# Sheet2.net
KiCad netlist of a schematic drawn in Altium Designer
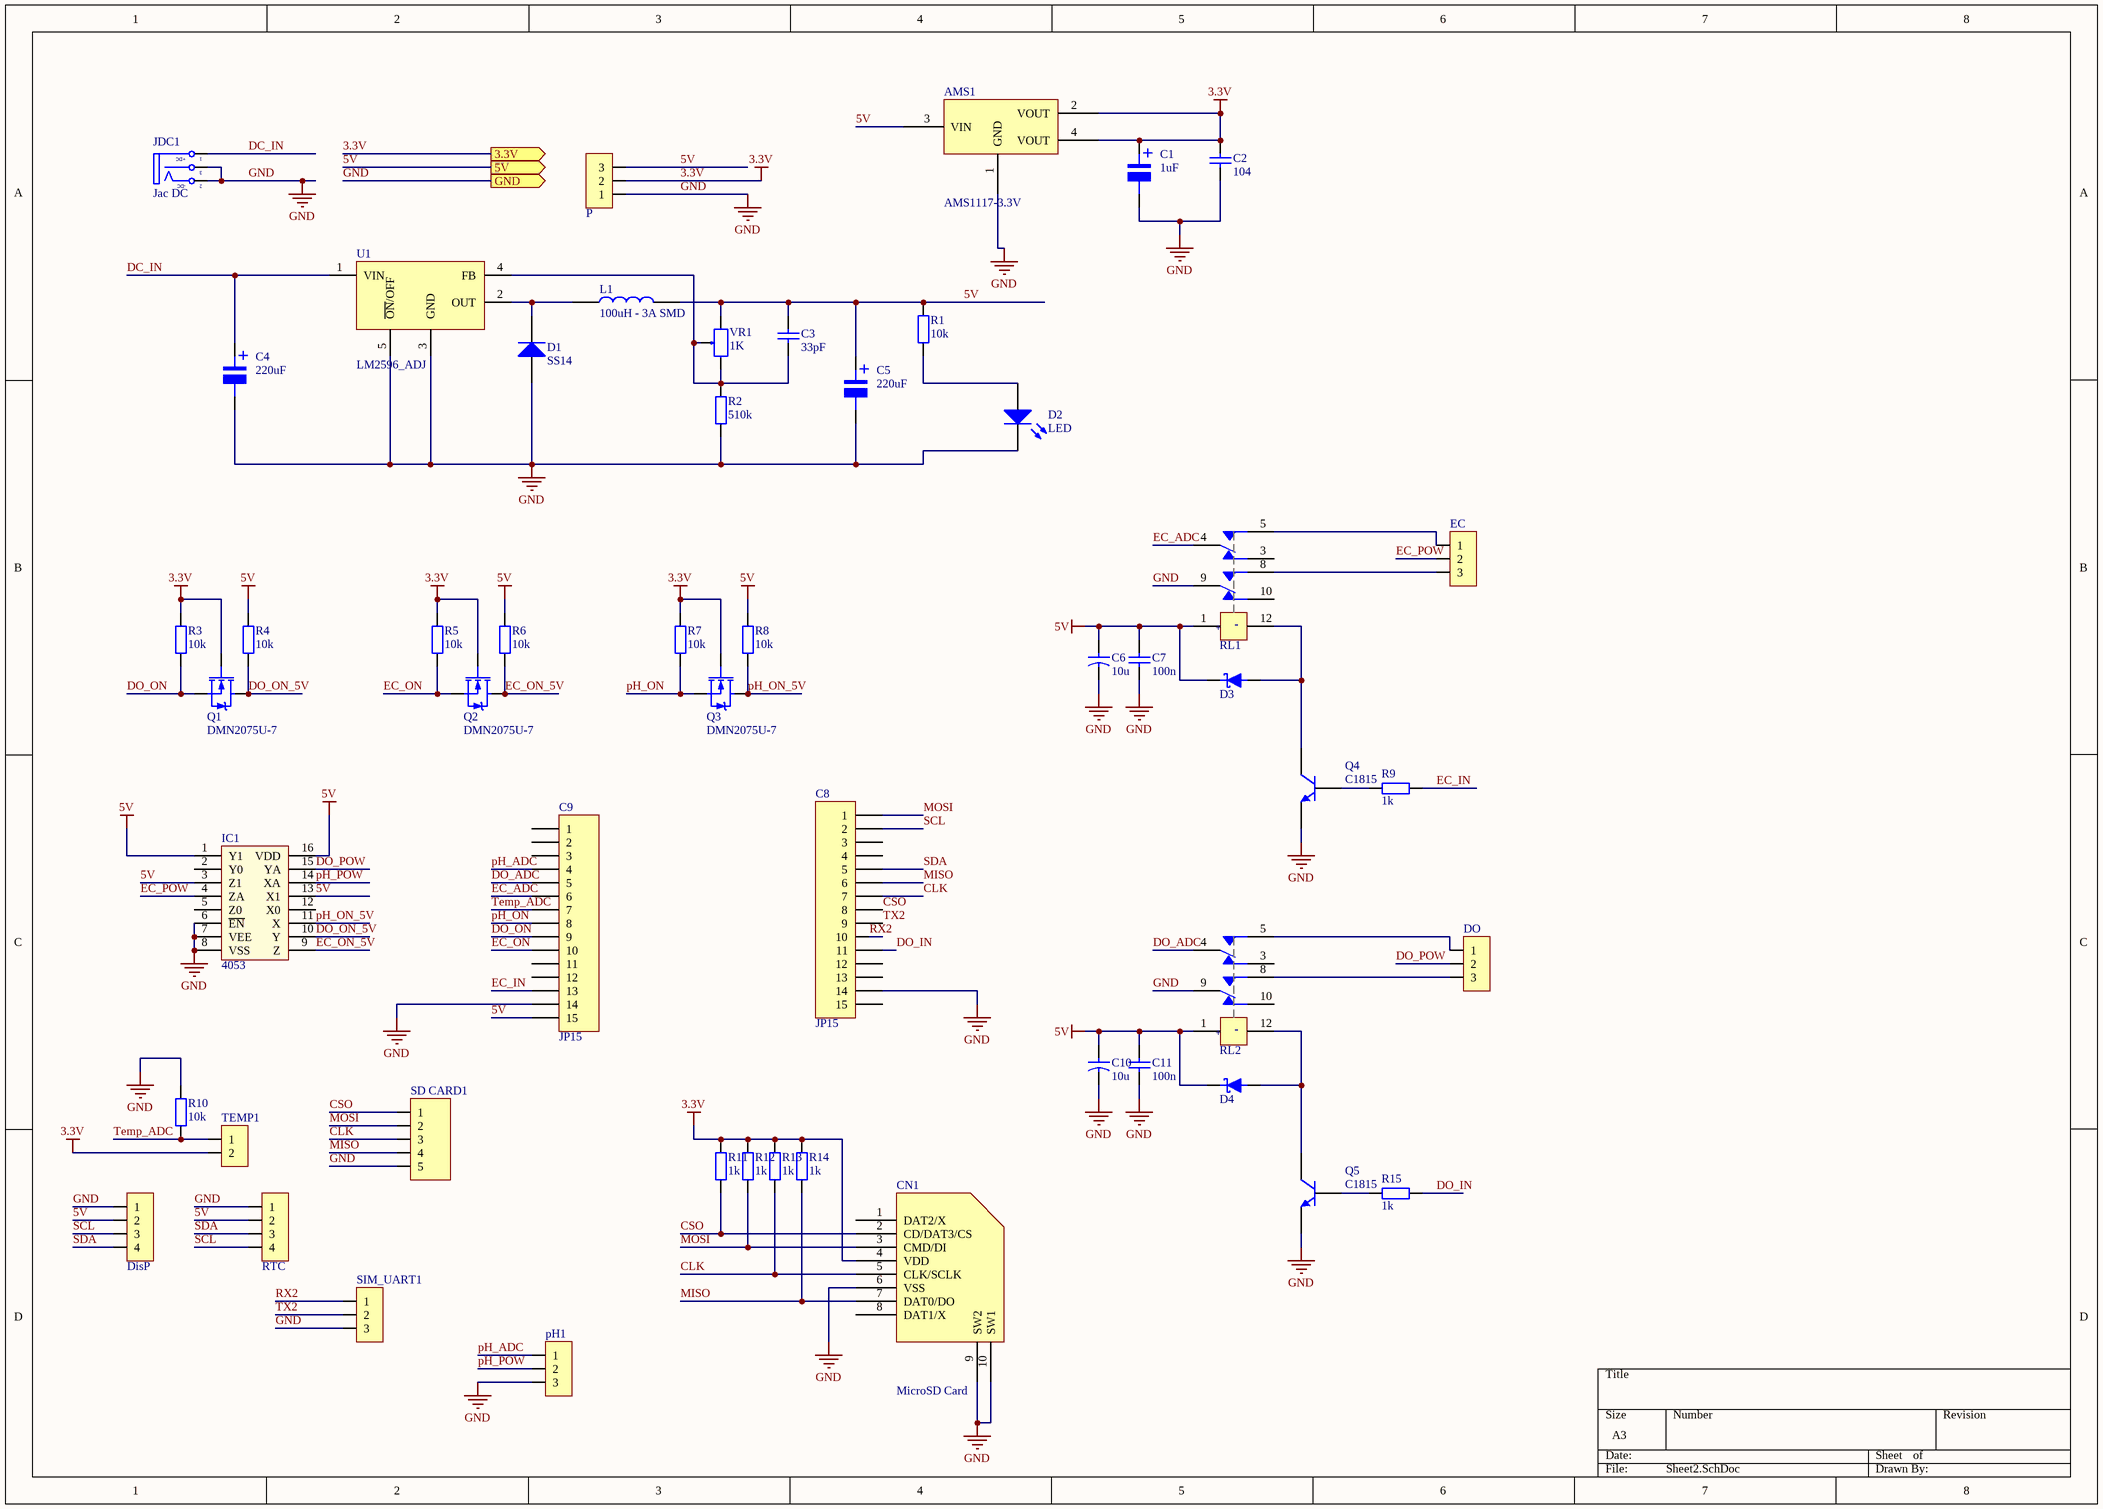
[diagram p0: Sheet2.SchDoc]

(export (version "E")
  (design (tool "Eeschema 10.0.6"))
  (components
    (comp (ref "AMS1")
      (value "AMS1117-3.3V")
      (footprint "SOT223")
      (description "Dán")
      (libsource (lib "bkres_POW") (part "AMS1117 SMD"))
    )
    (comp (ref "C1")
      (value "1uF")
      (footprint "tu nhom 4 (B)")
      (description "Dán")
      (libsource (lib "bkres_POW") (part "Tu Nhom 1uF 50V"))
    )
    (comp (ref "C2")
      (value "104")
      (footprint "tu 0805")
      (description "Dán")
      (libsource (lib "bkres_POW") (part "Tu 0805 104 50V 10%"))
    )
    (comp (ref "C3")
      (value "33pF")
      (footprint "tu 0805")
      (description "Dán")
      (libsource (lib "bkres_POW") (part "Tu 0805 33pF 50V 10%"))
    )
    (comp (ref "C4")
      (value "220uF")
      (footprint "tu nhom 6.3 (d)")
      (description "Dán")
      (libsource (lib "bkres_POW") (part "Tu Nhom 220uF 16V"))
    )
    (comp (ref "C5")
      (value "220uF")
      (footprint "tu nhom 6.3 (d)")
      (description "Dán")
      (libsource (lib "bkres_POW") (part "Tu Nhom 220uF 16V"))
    )
    (comp (ref "C6")
      (value "10u")
      (footprint "CT1206")
      (description "Polar Capacitor")
      (fields (field (name "Comment") "C-P"))
      (libsource (lib "Conductivity") (part "C-P"))
    )
    (comp (ref "C7")
      (value "100n")
      (footprint "CC0805L")
      (description "Non-Polar Capacitor")
      (fields (field (name "Comment") "C-N"))
      (libsource (lib "Conductivity") (part "C-N"))
    )
    (comp (ref "C8")
      (value "JP15")
      (footprint "JP15-C1T")
      (description "WR-PHD 2.54 mm Angled Socket Header")
      (fields
        (field (name "MANUFACTURER") "Würth Elektronik eiSos GmbH")
        (field (name "PARTNO") "613015143121")
        (field (name "CREATED BY") "Karrer Zheng")
      )
      (libsource (lib "") (part "JP15_1"))
    )
    (comp (ref "C9")
      (value "JP15")
      (footprint "JP15-C1T")
      (description "WR-PHD 2.54 mm Angled Socket Header")
      (fields
        (field (name "MANUFACTURER") "Würth Elektronik eiSos GmbH")
        (field (name "PARTNO") "613015143121")
        (field (name "CREATED BY") "Karrer Zheng")
      )
      (libsource (lib "LIBRARY") (part "JP15"))
    )
    (comp (ref "C10")
      (value "10u")
      (footprint "CT1206")
      (description "Polar Capacitor")
      (fields (field (name "Comment") "C-P"))
      (libsource (lib "Conductivity") (part "C-P"))
    )
    (comp (ref "C11")
      (value "100n")
      (footprint "CC0805L")
      (description "Non-Polar Capacitor")
      (fields (field (name "Comment") "C-N"))
      (libsource (lib "Conductivity") (part "C-N"))
    )
    (comp (ref "CN1")
      (value "MicroSD Card")
      (footprint "MicroSD Card")
      (libsource (lib "PCB_Project_5") (part "MicroSD Card"))
    )
    (comp (ref "D1")
      (value "SS14")
      (footprint "DIODE SMA")
      (description "Dán")
      (libsource (lib "bkres_POW") (part "Diode SS14 ( 1N5819)"))
    )
    (comp (ref "D2")
      (value "LED")
      (footprint "LED-0805-Red")
      (description "Typical INFRARED GaAs LED")
      (fields (field (name "PUBLISHER") "Altium Limited"))
      (libsource (lib "bkres_POW") (part "LED"))
    )
    (comp (ref "D3")
      (value "D Schottky")
      (footprint "DO-214AC")
      (description "Schottky Diode")
      (libsource (lib "Conductivity") (part "D Schottky"))
    )
    (comp (ref "D4")
      (value "D Schottky")
      (footprint "DO-214AC")
      (description "Schottky Diode")
      (libsource (lib "Conductivity") (part "D Schottky"))
    )
    (comp (ref "IC1")
      (value "4053")
      (footprint "SO16")
      (description "Dual 4-channel analogue  multiplexer/demultiplexer")
      (libsource (lib "TechMT.VN_Lib_Project v2") (part "4053"))
    )
    (comp (ref "JDC1")
      (value "Jac DC")
      (footprint "DC-IN")
      (description "Jac DC input")
      (libsource (lib "bkres_POW") (part "DCIN"))
    )
    (comp (ref "JP1")
      (value "DisP")
      (footprint "JP 1x4 CT")
      (description "Cắm")
      (libsource (lib "Altium_Lib_by_KhueNguyenCreator") (part "JP 1x4 2.54 Cai Thang"))
    )
    (comp (ref "JP2")
      (value "EC")
      (footprint "JP 1x3 DT")
      (description "Cắm")
      (libsource (lib "Altium_Lib_by_KhueNguyenCreator") (part "JP 1x3 2.54 Duc Thang"))
    )
    (comp (ref "JP3")
      (value "DO")
      (footprint "JP 1x3 DT")
      (description "Cắm")
      (libsource (lib "Altium_Lib_by_KhueNguyenCreator") (part "JP 1x3 2.54 Duc Thang"))
    )
    (comp (ref "JP4")
      (value "RTC")
      (footprint "JP 1x4 CT")
      (description "Cắm")
      (libsource (lib "Altium_Lib_by_KhueNguyenCreator") (part "JP 1x4 2.54 Cai Thang"))
    )
    (comp (ref "L1")
      (value "100uH - 3A SMD")
      (footprint "Cuon Cam 12x12x10")
      (description "Dán")
      (libsource (lib "bkres_POW") (part "CUON CAM 100uH SMD"))
    )
    (comp (ref "P")
      (value "SIM_UART")
      (footprint "JP 1x3 DT")
      (description "Cắm")
      (libsource (lib "") (part "JP 1x3 2.54 Duc Thang_1"))
    )
    (comp (ref "pH1")
      (value "pH")
      (footprint "JP 1x3 DT")
      (description "Cắm")
      (libsource (lib "Altium_Lib_by_KhueNguyenCreator") (part "JP 1x3 2.54 Duc Thang"))
    )
    (comp (ref "Q1")
      (value "DMN2075U-7")
      (footprint "SOT23")
      (description "MOSFET N-CH 20V 4.2A SOT23")
      (fields (field (name "PUBLISHER") "Altium Limited"))
      (libsource (lib "PCB_Project_5") (part "DMN2075U-7"))
    )
    (comp (ref "Q2")
      (value "DMN2075U-7")
      (footprint "SOT23")
      (description "MOSFET N-CH 20V 4.2A SOT23")
      (fields (field (name "PUBLISHER") "Altium Limited"))
      (libsource (lib "PCB_Project_5") (part "DMN2075U-7"))
    )
    (comp (ref "Q3")
      (value "DMN2075U-7")
      (footprint "SOT23")
      (description "MOSFET N-CH 20V 4.2A SOT23")
      (fields (field (name "PUBLISHER") "Altium Limited"))
      (libsource (lib "PCB_Project_5") (part "DMN2075U-7"))
    )
    (comp (ref "Q4")
      (value "C1815")
      (footprint "SOT-23")
      (description "NPN G, 150mA, 150MHz")
      (libsource (lib "Conductivity") (part "QC1815"))
    )
    (comp (ref "Q5")
      (value "C1815")
      (footprint "SOT-23")
      (description "NPN G, 150mA, 150MHz")
      (libsource (lib "Conductivity") (part "QC1815"))
    )
    (comp (ref "R1")
      (value "10k")
      (footprint "tro smd 0805")
      (description "Dán")
      (libsource (lib "bkres_POW") (part "Tro 0805 1% 10k"))
    )
    (comp (ref "R2")
      (value "510k")
      (footprint "tro smd 0805")
      (description "Dán")
      (libsource (lib "bkres_POW") (part "Tro 0805 1% 510k"))
    )
    (comp (ref "R3")
      (value "10k")
      (footprint "tro smd 0805")
      (description "Dán")
      (libsource (lib "Altium_Lib_by_KhueNguyenCreator") (part "Tro 0805 1% 1k"))
    )
    (comp (ref "R4")
      (value "10k")
      (footprint "tro smd 0805")
      (description "Dán")
      (libsource (lib "Altium_Lib_by_KhueNguyenCreator") (part "Tro 0805 1% 1k"))
    )
    (comp (ref "R5")
      (value "10k")
      (footprint "tro smd 0805")
      (description "Dán")
      (libsource (lib "Altium_Lib_by_KhueNguyenCreator") (part "Tro 0805 1% 1k"))
    )
    (comp (ref "R6")
      (value "10k")
      (footprint "tro smd 0805")
      (description "Dán")
      (libsource (lib "Altium_Lib_by_KhueNguyenCreator") (part "Tro 0805 1% 1k"))
    )
    (comp (ref "R7")
      (value "10k")
      (footprint "tro smd 0805")
      (description "Dán")
      (libsource (lib "Altium_Lib_by_KhueNguyenCreator") (part "Tro 0805 1% 1k"))
    )
    (comp (ref "R8")
      (value "10k")
      (footprint "tro smd 0805")
      (description "Dán")
      (libsource (lib "Altium_Lib_by_KhueNguyenCreator") (part "Tro 0805 1% 1k"))
    )
    (comp (ref "R9")
      (value "1k")
      (footprint "tro smd 0805")
      (description "Dán")
      (libsource (lib "Altium_Lib_by_KhueNguyenCreator") (part "Tro 0805 1% 1k"))
    )
    (comp (ref "R10")
      (value "10k")
      (footprint "tro smd 0805")
      (description "Dán")
      (libsource (lib "Altium_Lib_by_KhueNguyenCreator") (part "Tro 0805 1% 10k"))
    )
    (comp (ref "R11")
      (value "1k")
      (footprint "tro smd 0805")
      (description "Dán")
      (libsource (lib "Altium_Lib_by_KhueNguyenCreator") (part "Tro 0805 1% 1k"))
    )
    (comp (ref "R12")
      (value "1k")
      (footprint "tro smd 0805")
      (description "Dán")
      (libsource (lib "Altium_Lib_by_KhueNguyenCreator") (part "Tro 0805 1% 1k"))
    )
    (comp (ref "R13")
      (value "1k")
      (footprint "tro smd 0805")
      (description "Dán")
      (libsource (lib "Altium_Lib_by_KhueNguyenCreator") (part "Tro 0805 1% 1k"))
    )
    (comp (ref "R14")
      (value "1k")
      (footprint "tro smd 0805")
      (description "Dán")
      (libsource (lib "Altium_Lib_by_KhueNguyenCreator") (part "Tro 0805 1% 1k"))
    )
    (comp (ref "R15")
      (value "1k")
      (footprint "tro smd 0805")
      (description "Dán")
      (libsource (lib "Altium_Lib_by_KhueNguyenCreator") (part "Tro 0805 1% 1k"))
    )
    (comp (ref "RL1")
      (value "RL-G6S-2")
      (footprint "RL_G6S-2")
      (libsource (lib "Conductivity") (part "RL-G6S-2"))
    )
    (comp (ref "RL2")
      (value "RL-G6S-2")
      (footprint "RL_G6S-2")
      (libsource (lib "Conductivity") (part "RL-G6S-2"))
    )
    (comp (ref "SD CARD1")
      (value "JP 1x5 2.54")
      (footprint "JP 1x5 DT")
      (description "Cắm")
      (libsource (lib "Altium_Lib_by_KhueNguyenCreator") (part "JP 1x5 2.54 Duc Thang"))
    )
    (comp (ref "SIM_UART1")
      (value "SIM_UART")
      (footprint "JP 1x3 DT")
      (description "Cắm")
      (libsource (lib "Altium_Lib_by_KhueNguyenCreator") (part "JP 1x3 2.54 Duc Thang"))
    )
    (comp (ref "TEMP1")
      (value "JP 1x2 2.54")
      (footprint "JP 1x2 DT")
      (description "Cắm")
      (libsource (lib "Altium_Lib_by_KhueNguyenCreator") (part "JP 1x2 2.54 Duc Thang"))
    )
    (comp (ref "U1")
      (value "LM2596_ADJ")
      (footprint "TO263-5")
      (libsource (lib "bkres_POW") (part "LM2596_ADJ"))
    )
    (comp (ref "VR1")
      (value "1K")
      (footprint "Bien Tro Vi Chinh Dung")
      (description "Cắm")
      (libsource (lib "bkres_POW") (part "Bien Tro Tinh Chinh 1K Dung"))
    )
  )
  (nets
    (net (code "1") (name "/CLK") (class "Default")
      (node (ref "C8") (pin "7") (pinfunction "7_7") (pintype "passive"))
      (node (ref "CN1") (pin "5") (pinfunction "CLK/SCLK_5") (pintype "passive"))
      (node (ref "R13") (pin "1") (pinfunction "1_1") (pintype "passive"))
      (node (ref "SD CARD1") (pin "3") (pinfunction "3_3") (pintype "passive"))
    )
    (net (code "2") (name "/CSO") (class "Default")
      (node (ref "C8") (pin "8") (pinfunction "8_8") (pintype "passive"))
      (node (ref "CN1") (pin "2") (pinfunction "CD/DAT3/CS_2") (pintype "passive"))
      (node (ref "R11") (pin "1") (pinfunction "1_1") (pintype "passive"))
      (node (ref "SD CARD1") (pin "1") (pinfunction "1_1") (pintype "passive"))
    )
    (net (code "3") (name "/DC_IN") (class "Default")
      (node (ref "C4") (pin "1") (pinfunction "1_1") (pintype "passive"))
      (node (ref "JDC1") (pin "1") (pinfunction "T_1") (pintype "passive"))
      (node (ref "U1") (pin "1") (pinfunction "VIN_1") (pintype "power_in"))
    )
    (net (code "4") (name "/DO_ADC") (class "Default")
      (node (ref "C9") (pin "5") (pinfunction "5_5") (pintype "passive"))
      (node (ref "RL2") (pin "4") (pinfunction "2_4") (pintype "passive"))
    )
    (net (code "5") (name "/DO_IN") (class "Default")
      (node (ref "C8") (pin "11") (pinfunction "11_11") (pintype "passive"))
      (node (ref "R15") (pin "2") (pinfunction "2_2") (pintype "passive"))
    )
    (net (code "6") (name "/DO_ON") (class "Default")
      (node (ref "C9") (pin "9") (pinfunction "9_9") (pintype "passive"))
      (node (ref "Q1") (pin "2") (pinfunction "S_2") (pintype "passive"))
      (node (ref "R3") (pin "1") (pinfunction "1_1") (pintype "passive"))
    )
    (net (code "7") (name "/DO_ON_5V") (class "Default")
      (node (ref "IC1") (pin "10") (pinfunction "Y_10") (pintype "passive"))
      (node (ref "Q1") (pin "3") (pinfunction "D_3") (pintype "passive"))
      (node (ref "R4") (pin "1") (pinfunction "1_1") (pintype "passive"))
    )
    (net (code "8") (name "/DO_POW") (class "Default")
      (node (ref "IC1") (pin "15") (pinfunction "YA_15") (pintype "passive"))
      (node (ref "JP3") (pin "2") (pinfunction "2_2") (pintype "passive"))
    )
    (net (code "9") (name "/EC_ADC") (class "Default")
      (node (ref "C9") (pin "6") (pinfunction "6_6") (pintype "passive"))
      (node (ref "RL1") (pin "4") (pinfunction "2_4") (pintype "passive"))
    )
    (net (code "10") (name "/EC_IN") (class "Default")
      (node (ref "C9") (pin "13") (pinfunction "13_13") (pintype "passive"))
      (node (ref "R9") (pin "2") (pinfunction "2_2") (pintype "passive"))
    )
    (net (code "11") (name "/EC_ON") (class "Default")
      (node (ref "C9") (pin "10") (pinfunction "10_10") (pintype "passive"))
      (node (ref "Q2") (pin "2") (pinfunction "S_2") (pintype "passive"))
      (node (ref "R5") (pin "1") (pinfunction "1_1") (pintype "passive"))
    )
    (net (code "12") (name "/EC_ON_5V") (class "Default")
      (node (ref "IC1") (pin "9") (pinfunction "Z_9") (pintype "passive"))
      (node (ref "Q2") (pin "3") (pinfunction "D_3") (pintype "passive"))
      (node (ref "R6") (pin "1") (pinfunction "1_1") (pintype "passive"))
    )
    (net (code "13") (name "/EC_POW") (class "Default")
      (node (ref "IC1") (pin "4") (pinfunction "ZA_4") (pintype "passive"))
      (node (ref "JP2") (pin "2") (pinfunction "2_2") (pintype "passive"))
    )
    (net (code "14") (name "/MISO") (class "Default")
      (node (ref "C8") (pin "6") (pinfunction "6_6") (pintype "passive"))
      (node (ref "CN1") (pin "7") (pinfunction "DAT0/DO_7") (pintype "passive"))
      (node (ref "R14") (pin "1") (pinfunction "1_1") (pintype "passive"))
      (node (ref "SD CARD1") (pin "4") (pinfunction "4_4") (pintype "passive"))
    )
    (net (code "15") (name "/MOSI") (class "Default")
      (node (ref "C8") (pin "1") (pinfunction "1_1") (pintype "passive"))
      (node (ref "CN1") (pin "3") (pinfunction "CMD/DI_3") (pintype "passive"))
      (node (ref "R12") (pin "1") (pinfunction "1_1") (pintype "passive"))
      (node (ref "SD CARD1") (pin "2") (pinfunction "2_2") (pintype "passive"))
    )
    (net (code "16") (name "/RX2") (class "Default")
      (node (ref "C8") (pin "10") (pinfunction "10_10") (pintype "passive"))
      (node (ref "SIM_UART1") (pin "1") (pinfunction "1_1") (pintype "passive"))
    )
    (net (code "17") (name "/SCL") (class "Default")
      (node (ref "C8") (pin "2") (pinfunction "2_2") (pintype "passive"))
      (node (ref "JP1") (pin "3") (pinfunction "3_3") (pintype "passive"))
      (node (ref "JP4") (pin "4") (pinfunction "4_4") (pintype "passive"))
    )
    (net (code "18") (name "/SDA") (class "Default")
      (node (ref "C8") (pin "5") (pinfunction "5_5") (pintype "passive"))
      (node (ref "JP1") (pin "4") (pinfunction "4_4") (pintype "passive"))
      (node (ref "JP4") (pin "3") (pinfunction "3_3") (pintype "passive"))
    )
    (net (code "19") (name "/TX2") (class "Default")
      (node (ref "C8") (pin "9") (pinfunction "9_9") (pintype "passive"))
      (node (ref "SIM_UART1") (pin "2") (pinfunction "2_2") (pintype "passive"))
    )
    (net (code "20") (name "/Temp_ADC") (class "Default")
      (node (ref "C9") (pin "7") (pinfunction "7_7") (pintype "passive"))
      (node (ref "R10") (pin "1") (pinfunction "1_1") (pintype "passive"))
      (node (ref "TEMP1") (pin "1") (pinfunction "1_1") (pintype "passive"))
    )
    (net (code "21") (name "/pH_ADC") (class "Default")
      (node (ref "C9") (pin "4") (pinfunction "4_4") (pintype "passive"))
      (node (ref "pH1") (pin "1") (pinfunction "1_1") (pintype "passive"))
    )
    (net (code "22") (name "/pH_ON") (class "Default")
      (node (ref "C9") (pin "8") (pinfunction "8_8") (pintype "passive"))
      (node (ref "Q3") (pin "2") (pinfunction "S_2") (pintype "passive"))
      (node (ref "R7") (pin "1") (pinfunction "1_1") (pintype "passive"))
    )
    (net (code "23") (name "/pH_ON_5V") (class "Default")
      (node (ref "IC1") (pin "11") (pinfunction "X_11") (pintype "passive"))
      (node (ref "Q3") (pin "3") (pinfunction "D_3") (pintype "passive"))
      (node (ref "R8") (pin "1") (pinfunction "1_1") (pintype "passive"))
    )
    (net (code "24") (name "/pH_POW") (class "Default")
      (node (ref "IC1") (pin "14") (pinfunction "XA_14") (pintype "passive"))
      (node (ref "pH1") (pin "2") (pinfunction "2_2") (pintype "passive"))
    )
    (net (code "25") (name "3.3V") (class "Default")
      (node (ref "AMS1") (pin "2") (pinfunction "VOUT_2") (pintype "passive"))
      (node (ref "AMS1") (pin "4") (pinfunction "VOUT_4") (pintype "passive"))
      (node (ref "C1") (pin "1") (pinfunction "1_1") (pintype "passive"))
      (node (ref "C2") (pin "1") (pinfunction "1_1") (pintype "passive"))
      (node (ref "CN1") (pin "4") (pinfunction "VDD_4") (pintype "passive"))
      (node (ref "P") (pin "2") (pinfunction "2_2") (pintype "passive"))
      (node (ref "Q1") (pin "1") (pinfunction "G_1") (pintype "passive"))
      (node (ref "Q2") (pin "1") (pinfunction "G_1") (pintype "passive"))
      (node (ref "Q3") (pin "1") (pinfunction "G_1") (pintype "passive"))
      (node (ref "R11") (pin "2") (pinfunction "2_2") (pintype "passive"))
      (node (ref "R12") (pin "2") (pinfunction "2_2") (pintype "passive"))
      (node (ref "R13") (pin "2") (pinfunction "2_2") (pintype "passive"))
      (node (ref "R14") (pin "2") (pinfunction "2_2") (pintype "passive"))
      (node (ref "R3") (pin "2") (pinfunction "2_2") (pintype "passive"))
      (node (ref "R5") (pin "2") (pinfunction "2_2") (pintype "passive"))
      (node (ref "R7") (pin "2") (pinfunction "2_2") (pintype "passive"))
      (node (ref "TEMP1") (pin "2") (pinfunction "2_2") (pintype "passive"))
    )
    (net (code "26") (name "5V") (class "Default")
      (node (ref "AMS1") (pin "3") (pinfunction "VIN_3") (pintype "passive"))
      (node (ref "C10") (pin "1") (pinfunction "1_1") (pintype "passive"))
      (node (ref "C11") (pin "2") (pinfunction "2_2") (pintype "passive"))
      (node (ref "C3") (pin "1") (pinfunction "1_1") (pintype "passive"))
      (node (ref "C5") (pin "1") (pinfunction "1_1") (pintype "passive"))
      (node (ref "C6") (pin "1") (pinfunction "1_1") (pintype "passive"))
      (node (ref "C7") (pin "2") (pinfunction "2_2") (pintype "passive"))
      (node (ref "C9") (pin "15") (pinfunction "15_15") (pintype "passive"))
      (node (ref "D3") (pin "2") (pinfunction "K_2") (pintype "passive"))
      (node (ref "D4") (pin "2") (pinfunction "K_2") (pintype "passive"))
      (node (ref "IC1") (pin "1") (pinfunction "Y1_1") (pintype "passive"))
      (node (ref "IC1") (pin "13") (pinfunction "X1_13") (pintype "passive"))
      (node (ref "IC1") (pin "16") (pinfunction "VDD_16") (pintype "passive"))
      (node (ref "IC1") (pin "3") (pinfunction "Z1_3") (pintype "passive"))
      (node (ref "JP1") (pin "2") (pinfunction "2_2") (pintype "passive"))
      (node (ref "JP4") (pin "2") (pinfunction "2_2") (pintype "passive"))
      (node (ref "L1") (pin "2") (pinfunction "2_2") (pintype "passive"))
      (node (ref "P") (pin "3") (pinfunction "3_3") (pintype "passive"))
      (node (ref "R1") (pin "2") (pinfunction "2_2") (pintype "passive"))
      (node (ref "R4") (pin "2") (pinfunction "2_2") (pintype "passive"))
      (node (ref "R6") (pin "2") (pinfunction "2_2") (pintype "passive"))
      (node (ref "R8") (pin "2") (pinfunction "2_2") (pintype "passive"))
      (node (ref "RL1") (pin "1") (pintype "passive"))
      (node (ref "RL2") (pin "1") (pintype "passive"))
      (node (ref "VR1") (pin "3") (pinfunction "3_3") (pintype "passive"))
    )
    (net (code "27") (name "GND") (class "Default")
      (node (ref "AMS1") (pin "1") (pinfunction "GND_1") (pintype "passive"))
      (node (ref "C1") (pin "2") (pinfunction "2_2") (pintype "passive"))
      (node (ref "C10") (pin "2") (pinfunction "2_2") (pintype "passive"))
      (node (ref "C11") (pin "1") (pinfunction "1_1") (pintype "passive"))
      (node (ref "C2") (pin "2") (pinfunction "2_2") (pintype "passive"))
      (node (ref "C4") (pin "2") (pinfunction "2_2") (pintype "passive"))
      (node (ref "C5") (pin "2") (pinfunction "2_2") (pintype "passive"))
      (node (ref "C6") (pin "2") (pinfunction "2_2") (pintype "passive"))
      (node (ref "C7") (pin "1") (pinfunction "1_1") (pintype "passive"))
      (node (ref "C8") (pin "14") (pinfunction "14_14") (pintype "passive"))
      (node (ref "C9") (pin "14") (pinfunction "14_14") (pintype "passive"))
      (node (ref "CN1") (pin "10") (pinfunction "SW1_10") (pintype "passive"))
      (node (ref "CN1") (pin "6") (pinfunction "VSS_6") (pintype "passive"))
      (node (ref "CN1") (pin "9") (pinfunction "SW2_9") (pintype "passive"))
      (node (ref "D1") (pin "1") (pinfunction "A_1") (pintype "passive"))
      (node (ref "D2") (pin "2") (pinfunction "K_2") (pintype "passive"))
      (node (ref "IC1") (pin "6") (pinfunction "~{EN}_6") (pintype "passive"))
      (node (ref "IC1") (pin "7") (pinfunction "VEE_7") (pintype "passive"))
      (node (ref "IC1") (pin "8") (pinfunction "VSS_8") (pintype "passive"))
      (node (ref "JDC1") (pin "2") (pinfunction "TN_2") (pintype "passive"))
      (node (ref "JDC1") (pin "3") (pinfunction "S_3") (pintype "power_in"))
      (node (ref "JP1") (pin "1") (pinfunction "1_1") (pintype "passive"))
      (node (ref "JP4") (pin "1") (pinfunction "1_1") (pintype "passive"))
      (node (ref "P") (pin "1") (pinfunction "1_1") (pintype "passive"))
      (node (ref "Q4") (pin "1") (pinfunction "E_1") (pintype "passive"))
      (node (ref "Q5") (pin "1") (pinfunction "E_1") (pintype "passive"))
      (node (ref "R10") (pin "2") (pinfunction "2_2") (pintype "passive"))
      (node (ref "R2") (pin "1") (pinfunction "1_1") (pintype "passive"))
      (node (ref "RL1") (pin "9") (pinfunction "5_9") (pintype "passive"))
      (node (ref "RL2") (pin "9") (pinfunction "5_9") (pintype "passive"))
      (node (ref "SD CARD1") (pin "5") (pinfunction "5_5") (pintype "passive"))
      (node (ref "SIM_UART1") (pin "3") (pinfunction "3_3") (pintype "passive"))
      (node (ref "U1") (pin "3") (pinfunction "GND_3") (pintype "power_in"))
      (node (ref "U1") (pin "5") (pinfunction "~{ON}/OFF_5") (pintype "power_in"))
      (node (ref "pH1") (pin "3") (pinfunction "3_3") (pintype "passive"))
    )
    (net (code "28") (name "Net-(D1-K)") (class "Default")
      (node (ref "D1") (pin "2") (pinfunction "K_2") (pintype "passive"))
      (node (ref "L1") (pin "1") (pinfunction "1_1") (pintype "passive"))
      (node (ref "U1") (pin "2") (pinfunction "OUT_2") (pintype "power_in"))
    )
    (net (code "29") (name "Net-(D2-A)") (class "Default")
      (node (ref "D2") (pin "1") (pinfunction "A_1") (pintype "passive"))
      (node (ref "R1") (pin "1") (pinfunction "1_1") (pintype "passive"))
    )
    (net (code "30") (name "Net-(D3-A)") (class "Default")
      (node (ref "D3") (pin "1") (pinfunction "A_1") (pintype "passive"))
      (node (ref "Q4") (pin "2") (pinfunction "C_2") (pintype "passive"))
      (node (ref "RL1") (pin "12") (pintype "passive"))
    )
    (net (code "31") (name "Net-(D4-A)") (class "Default")
      (node (ref "D4") (pin "1") (pinfunction "A_1") (pintype "passive"))
      (node (ref "Q5") (pin "2") (pinfunction "C_2") (pintype "passive"))
      (node (ref "RL2") (pin "12") (pintype "passive"))
    )
    (net (code "32") (name "Net-(JP2-Pad1)") (class "Default")
      (node (ref "JP2") (pin "1") (pinfunction "1_1") (pintype "passive"))
      (node (ref "RL1") (pin "5") (pinfunction "5_5") (pintype "passive"))
    )
    (net (code "33") (name "Net-(JP2-Pad3)") (class "Default")
      (node (ref "JP2") (pin "3") (pinfunction "3_3") (pintype "passive"))
      (node (ref "RL1") (pin "8") (pinfunction "8_8") (pintype "passive"))
    )
    (net (code "34") (name "Net-(JP3-Pad1)") (class "Default")
      (node (ref "JP3") (pin "1") (pinfunction "1_1") (pintype "passive"))
      (node (ref "RL2") (pin "5") (pinfunction "5_5") (pintype "passive"))
    )
    (net (code "35") (name "Net-(JP3-Pad3)") (class "Default")
      (node (ref "JP3") (pin "3") (pinfunction "3_3") (pintype "passive"))
      (node (ref "RL2") (pin "8") (pinfunction "8_8") (pintype "passive"))
    )
    (net (code "36") (name "Net-(Q4-B)") (class "Default")
      (node (ref "Q4") (pin "3") (pinfunction "B_3") (pintype "passive"))
      (node (ref "R9") (pin "1") (pinfunction "1_1") (pintype "passive"))
    )
    (net (code "37") (name "Net-(Q5-B)") (class "Default")
      (node (ref "Q5") (pin "3") (pinfunction "B_3") (pintype "passive"))
      (node (ref "R15") (pin "1") (pinfunction "1_1") (pintype "passive"))
    )
    (net (code "38") (name "Net-(U1-FB)") (class "Default")
      (node (ref "C3") (pin "2") (pinfunction "2_2") (pintype "passive"))
      (node (ref "R2") (pin "2") (pinfunction "2_2") (pintype "passive"))
      (node (ref "U1") (pin "4") (pinfunction "FB_4") (pintype "power_in"))
      (node (ref "VR1") (pin "1") (pinfunction "1_1") (pintype "passive"))
      (node (ref "VR1") (pin "2") (pinfunction "2_2") (pintype "passive"))
    )
    (net (code "39") (name "unconnected-(C8-Pad3)") (class "Default")
      (node (ref "C8") (pin "3") (pinfunction "3_3") (pintype "passive"))
    )
    (net (code "40") (name "unconnected-(C8-Pad4)") (class "Default")
      (node (ref "C8") (pin "4") (pinfunction "4_4") (pintype "passive"))
    )
    (net (code "41") (name "unconnected-(C8-Pad12)") (class "Default")
      (node (ref "C8") (pin "12") (pinfunction "12_12") (pintype "passive"))
    )
    (net (code "42") (name "unconnected-(C8-Pad13)") (class "Default")
      (node (ref "C8") (pin "13") (pinfunction "13_13") (pintype "passive"))
    )
    (net (code "43") (name "unconnected-(C8-Pad15)") (class "Default")
      (node (ref "C8") (pin "15") (pinfunction "15_15") (pintype "passive"))
    )
    (net (code "44") (name "unconnected-(C9-Pad1)") (class "Default")
      (node (ref "C9") (pin "1") (pinfunction "1_1") (pintype "passive"))
    )
    (net (code "45") (name "unconnected-(C9-Pad2)") (class "Default")
      (node (ref "C9") (pin "2") (pinfunction "2_2") (pintype "passive"))
    )
    (net (code "46") (name "unconnected-(C9-Pad3)") (class "Default")
      (node (ref "C9") (pin "3") (pinfunction "3_3") (pintype "passive"))
    )
    (net (code "47") (name "unconnected-(C9-Pad11)") (class "Default")
      (node (ref "C9") (pin "11") (pinfunction "11_11") (pintype "passive"))
    )
    (net (code "48") (name "unconnected-(C9-Pad12)") (class "Default")
      (node (ref "C9") (pin "12") (pinfunction "12_12") (pintype "passive"))
    )
    (net (code "49") (name "unconnected-(CN1-DAT1{slash}X-Pad8)") (class "Default")
      (node (ref "CN1") (pin "8") (pinfunction "DAT1/X_8") (pintype "passive"))
    )
    (net (code "50") (name "unconnected-(CN1-DAT2{slash}X-Pad1)") (class "Default")
      (node (ref "CN1") (pin "1") (pinfunction "DAT2/X_1") (pintype "passive"))
    )
    (net (code "51") (name "unconnected-(IC1-X0-Pad12)") (class "Default")
      (node (ref "IC1") (pin "12") (pinfunction "X0_12") (pintype "passive"))
    )
    (net (code "52") (name "unconnected-(IC1-Y0-Pad2)") (class "Default")
      (node (ref "IC1") (pin "2") (pinfunction "Y0_2") (pintype "passive"))
    )
    (net (code "53") (name "unconnected-(IC1-Z0-Pad5)") (class "Default")
      (node (ref "IC1") (pin "5") (pinfunction "Z0_5") (pintype "passive"))
    )
    (net (code "54") (name "unconnected-(RL1-Pad3)") (class "Default")
      (node (ref "RL1") (pin "3") (pinfunction "3_3") (pintype "passive"))
    )
    (net (code "55") (name "unconnected-(RL1-Pad10)") (class "Default")
      (node (ref "RL1") (pin "10") (pinfunction "10_10") (pintype "passive"))
    )
    (net (code "56") (name "unconnected-(RL2-Pad3)") (class "Default")
      (node (ref "RL2") (pin "3") (pinfunction "3_3") (pintype "passive"))
    )
    (net (code "57") (name "unconnected-(RL2-Pad10)") (class "Default")
      (node (ref "RL2") (pin "10") (pinfunction "10_10") (pintype "passive"))
    )
  )
)
